# Gate_Driver_H-Bridge.net
KiCad netlist of a schematic drawn in Altium Designer
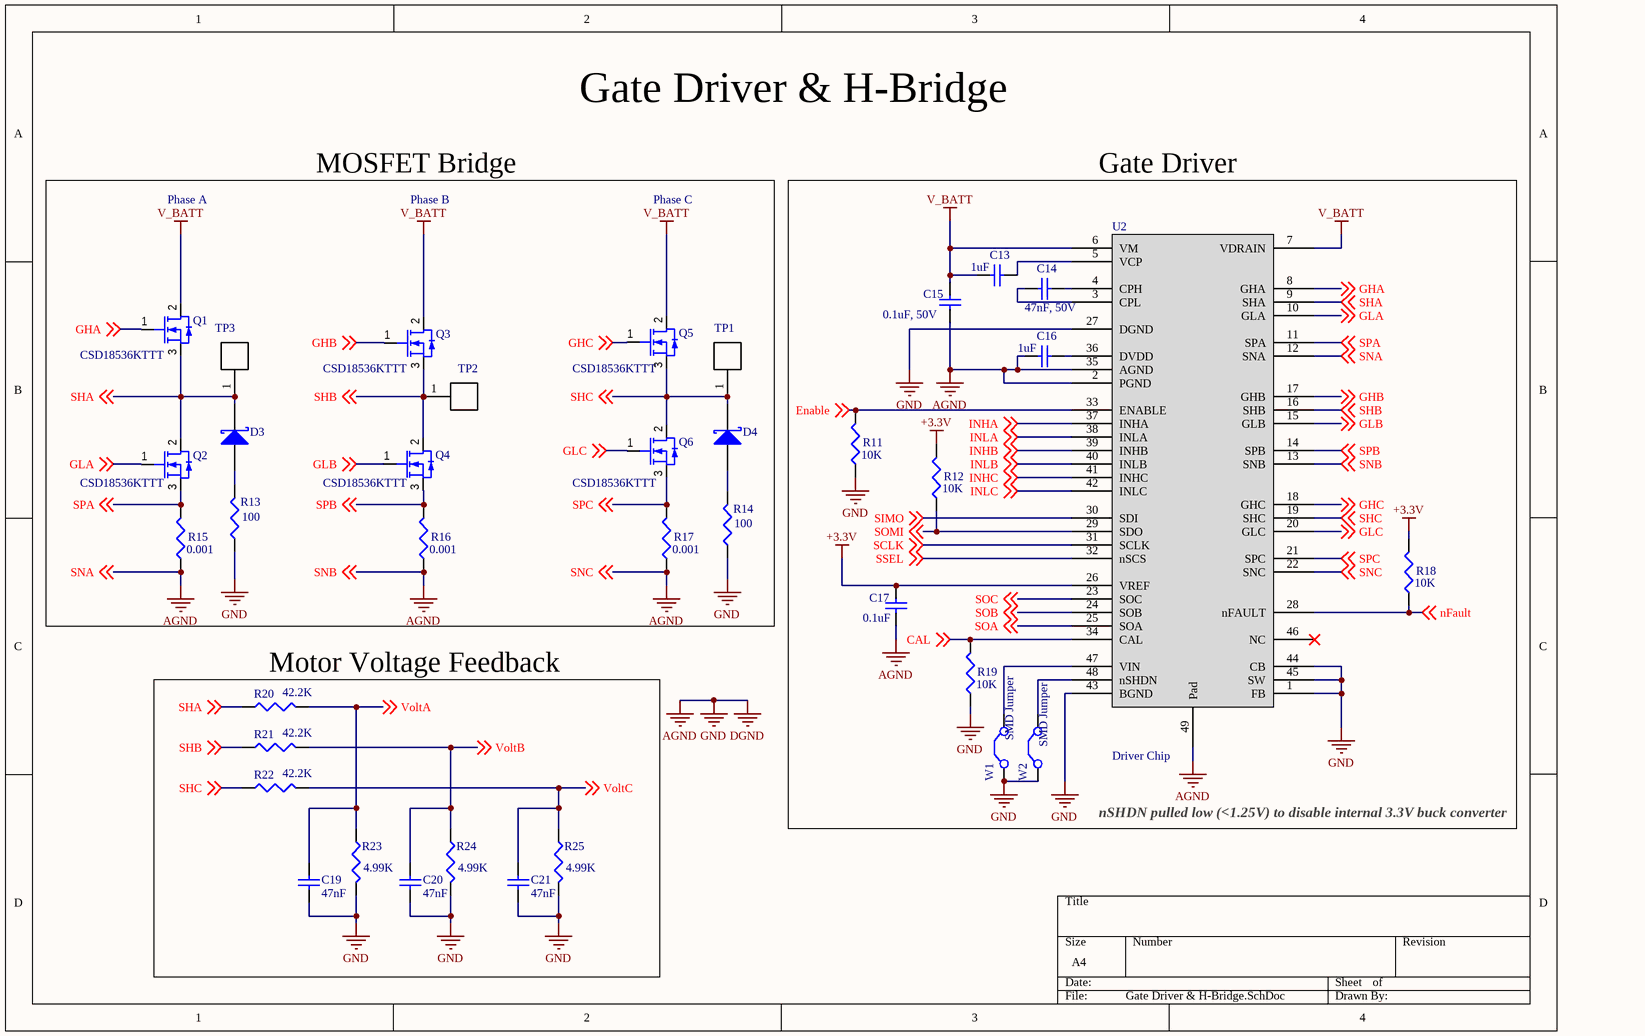
[diagram p0: Gate Driver & H-Bridge.SchDoc]

(export (version "E")
  (design (tool "Eeschema 10.0.6"))
  (components
    (comp (ref "C13")
      (value "1uF")
      (footprint "CAPC2012X06N")
      (description "Capacitor")
      (fields (field (name "Comment") "Cap") (field (name "PUBLISHER") "Altium Limited"))
      (libsource (lib "Miscellaneous Devices") (part "Cap"))
    )
    (comp (ref "C14")
      (value "47nF, 50V")
      (footprint "0603 CAP Medium")
      (description "Capacitor")
      (fields (field (name "Comment") "Cap") (field (name "PUBLISHER") "Altium Limited"))
      (libsource (lib "Miscellaneous Devices") (part "Cap"))
    )
    (comp (ref "C15")
      (value "0.1uF, 50V")
      (footprint "0603 CAP Medium")
      (description "Capacitor")
      (fields (field (name "Comment") "Cap") (field (name "PUBLISHER") "Altium Limited"))
      (libsource (lib "Miscellaneous Devices") (part "Cap"))
    )
    (comp (ref "C16")
      (value "1uF")
      (footprint "CAPC2012X06N")
      (description "Capacitor")
      (fields (field (name "Comment") "Cap") (field (name "PUBLISHER") "Altium Limited"))
      (libsource (lib "Miscellaneous Devices") (part "Cap"))
    )
    (comp (ref "C17")
      (value "0.1uF")
      (footprint "0603 CAP Medium")
      (description "Capacitor")
      (fields (field (name "Comment") "Cap") (field (name "PUBLISHER") "Altium Limited"))
      (libsource (lib "Miscellaneous Devices") (part "Cap"))
    )
    (comp (ref "C19")
      (value "47nF")
      (footprint "0603 CAP Medium")
      (description "Capacitor")
      (fields (field (name "Comment") "Cap") (field (name "PUBLISHER") "Altium Limited"))
      (libsource (lib "Miscellaneous Devices") (part "Cap"))
    )
    (comp (ref "C20")
      (value "47nF")
      (footprint "0603 CAP Medium")
      (description "Capacitor")
      (fields (field (name "Comment") "Cap") (field (name "PUBLISHER") "Altium Limited"))
      (libsource (lib "Miscellaneous Devices") (part "Cap"))
    )
    (comp (ref "C21")
      (value "47nF")
      (footprint "0603 CAP Medium")
      (description "Capacitor")
      (fields (field (name "Comment") "Cap") (field (name "PUBLISHER") "Altium Limited"))
      (libsource (lib "Miscellaneous Devices") (part "Cap"))
    )
    (comp (ref "D3")
      (value "Diode 11DQ03")
      (footprint "Zener")
      (description "Schottky Rectifier")
      (fields (field (name "PUBLISHER") "Altium Limited"))
      (libsource (lib "Miscellaneous Devices") (part "Diode 11DQ03"))
    )
    (comp (ref "D4")
      (value "Diode 11DQ03")
      (footprint "Zener")
      (description "Schottky Rectifier")
      (fields (field (name "PUBLISHER") "Altium Limited"))
      (libsource (lib "Miscellaneous Devices") (part "Diode 11DQ03"))
    )
    (comp (ref "Q1")
      (value "CSD18536KTTT")
      (footprint "DPAK254P1510X470-3M")
      (fields (field (name "MANUFACTURER") "Texas Instruments"))
      (libsource (lib "ECar Reference LIbary") (part "CSD18536KTTT"))
    )
    (comp (ref "Q2")
      (value "CSD18536KTTT")
      (footprint "DPAK254P1510X470-3M")
      (fields (field (name "MANUFACTURER") "Texas Instruments"))
      (libsource (lib "ECar Reference LIbary") (part "CSD18536KTTT"))
    )
    (comp (ref "Q3")
      (value "CSD18536KTTT")
      (footprint "DPAK254P1510X470-3M")
      (fields (field (name "MANUFACTURER") "Texas Instruments"))
      (libsource (lib "ECar Reference LIbary") (part "CSD18536KTTT"))
    )
    (comp (ref "Q4")
      (value "CSD18536KTTT")
      (footprint "DPAK254P1510X470-3M")
      (fields (field (name "MANUFACTURER") "Texas Instruments"))
      (libsource (lib "ECar Reference LIbary") (part "CSD18536KTTT"))
    )
    (comp (ref "Q5")
      (value "CSD18536KTTT")
      (footprint "DPAK254P1510X470-3M")
      (fields (field (name "MANUFACTURER") "Texas Instruments"))
      (libsource (lib "ECar Reference LIbary") (part "CSD18536KTTT"))
    )
    (comp (ref "Q6")
      (value "CSD18536KTTT")
      (footprint "DPAK254P1510X470-3M")
      (fields (field (name "MANUFACTURER") "Texas Instruments"))
      (libsource (lib "ECar Reference LIbary") (part "CSD18536KTTT"))
    )
    (comp (ref "R11")
      (value "10K")
      (footprint "RES 0603 MEDIUM")
      (description "Resistor")
      (fields (field (name "Comment") "Res3") (field (name "PUBLISHER") "Altium Limited"))
      (libsource (lib "Miscellaneous Devices") (part "Res3"))
    )
    (comp (ref "R12")
      (value "10K")
      (footprint "RES 0603 MEDIUM")
      (description "Resistor")
      (fields (field (name "Comment") "Res3") (field (name "PUBLISHER") "Altium Limited"))
      (libsource (lib "Miscellaneous Devices") (part "Res3"))
    )
    (comp (ref "R13")
      (value "100")
      (footprint "RES 0603 MEDIUM")
      (description "Resistor")
      (fields (field (name "Comment") "Res3") (field (name "PUBLISHER") "Altium Limited"))
      (libsource (lib "Miscellaneous Devices") (part "Res3"))
    )
    (comp (ref "R14")
      (value "100")
      (footprint "RES 0603 MEDIUM")
      (description "Resistor")
      (fields (field (name "Comment") "Res3") (field (name "PUBLISHER") "Altium Limited"))
      (libsource (lib "Miscellaneous Devices") (part "Res3"))
    )
    (comp (ref "R15")
      (value "0.001")
      (footprint "RESC8032X08N")
      (description "Resistor")
      (fields (field (name "Comment") "Res3") (field (name "PUBLISHER") "Altium Limited"))
      (libsource (lib "Miscellaneous Devices") (part "Res3"))
    )
    (comp (ref "R16")
      (value "0.001")
      (footprint "RESC8032X08N")
      (description "Resistor")
      (fields (field (name "Comment") "Res3") (field (name "PUBLISHER") "Altium Limited"))
      (libsource (lib "Miscellaneous Devices") (part "Res3"))
    )
    (comp (ref "R17")
      (value "0.001")
      (footprint "RESC8032X08N")
      (description "Resistor")
      (fields (field (name "Comment") "Res3") (field (name "PUBLISHER") "Altium Limited"))
      (libsource (lib "Miscellaneous Devices") (part "Res3"))
    )
    (comp (ref "R18")
      (value "10K")
      (footprint "RES 0603 MEDIUM")
      (description "Resistor")
      (fields (field (name "Comment") "Res3") (field (name "PUBLISHER") "Altium Limited"))
      (libsource (lib "Miscellaneous Devices") (part "Res3"))
    )
    (comp (ref "R19")
      (value "10K")
      (footprint "RES 0603 MEDIUM")
      (description "Resistor")
      (fields (field (name "Comment") "Res3") (field (name "PUBLISHER") "Altium Limited"))
      (libsource (lib "Miscellaneous Devices") (part "Res3"))
    )
    (comp (ref "R20")
      (value "42.2K")
      (footprint "RES 0603 MEDIUM")
      (description "Resistor")
      (fields (field (name "Comment") "Res3") (field (name "PUBLISHER") "Altium Limited"))
      (libsource (lib "Miscellaneous Devices") (part "Res3"))
    )
    (comp (ref "R21")
      (value "42.2K")
      (footprint "RES 0603 MEDIUM")
      (description "Resistor")
      (fields (field (name "Comment") "Res3") (field (name "PUBLISHER") "Altium Limited"))
      (libsource (lib "Miscellaneous Devices") (part "Res3"))
    )
    (comp (ref "R22")
      (value "42.2K")
      (footprint "RES 0603 MEDIUM")
      (description "Resistor")
      (fields (field (name "Comment") "Res3") (field (name "PUBLISHER") "Altium Limited"))
      (libsource (lib "Miscellaneous Devices") (part "Res3"))
    )
    (comp (ref "R23")
      (value "4.99K")
      (footprint "RES 0603 MEDIUM")
      (description "Resistor")
      (fields (field (name "Comment") "Res3") (field (name "PUBLISHER") "Altium Limited"))
      (libsource (lib "Miscellaneous Devices") (part "Res3"))
    )
    (comp (ref "R24")
      (value "4.99K")
      (footprint "RES 0603 MEDIUM")
      (description "Resistor")
      (fields (field (name "Comment") "Res3") (field (name "PUBLISHER") "Altium Limited"))
      (libsource (lib "Miscellaneous Devices") (part "Res3"))
    )
    (comp (ref "R25")
      (value "4.99K")
      (footprint "RES 0603 MEDIUM")
      (description "Resistor")
      (fields (field (name "Comment") "Res3") (field (name "PUBLISHER") "Altium Limited"))
      (libsource (lib "Miscellaneous Devices") (part "Res3"))
    )
    (comp (ref "TP1")
      (value "1625854-3")
      (footprint "TE_RCU-0C")
      (description "0603 PROBE PAD")
      (fields (field (name "MF") "TE Connectivity") (field (name "DIGI-KEY_PART_NUMBER") "A106145CT-ND"))
      (libsource (lib "ECar Reference LIbary") (part "RCU-0C"))
    )
    (comp (ref "TP2")
      (value "1625854-3")
      (footprint "TE_RCU-0C")
      (description "0603 PROBE PAD")
      (fields (field (name "MF") "TE Connectivity") (field (name "DIGI-KEY_PART_NUMBER") "A106145CT-ND"))
      (libsource (lib "ECar Reference LIbary") (part "RCU-0C"))
    )
    (comp (ref "TP3")
      (value "1625854-3")
      (footprint "TE_RCU-0C")
      (description "0603 PROBE PAD")
      (fields (field (name "MF") "TE Connectivity") (field (name "DIGI-KEY_PART_NUMBER") "A106145CT-ND"))
      (libsource (lib "ECar Reference LIbary") (part "RCU-0C"))
    )
    (comp (ref "U2")
      (value "Driver Chip")
      (footprint "QFN50P700X700X100_HS-49N")
      (libsource (lib "MOSFET Board Schematic Library") (part "Driver Chip"))
    )
    (comp (ref "W1")
      (value "SMD Jumper")
      (footprint "SMD Jumper")
      (description "SMD solder jumper")
      (libsource (lib "ECar Reference LIbary") (part "SMD Jumper"))
    )
    (comp (ref "W2")
      (value "SMD Jumper")
      (footprint "SMD Jumper")
      (description "SMD solder jumper")
      (libsource (lib "ECar Reference LIbary") (part "SMD Jumper"))
    )
  )
  (nets
    (net (code "1") (name "+3.3V") (class "Default")
      (node (ref "C17") (pin "2") (pinfunction "2_2") (pintype "passive"))
      (node (ref "R12") (pin "2") (pinfunction "2_2") (pintype "passive"))
      (node (ref "R18") (pin "2") (pinfunction "2_2") (pintype "passive"))
      (node (ref "U2") (pin "26") (pinfunction "VREF_26") (pintype "passive"))
    )
    (net (code "2") (name "AGND") (class "Default")
      (node (ref "C15") (pin "1") (pinfunction "1_1") (pintype "passive"))
      (node (ref "C16") (pin "1") (pinfunction "1_1") (pintype "passive"))
      (node (ref "C17") (pin "1") (pinfunction "1_1") (pintype "passive"))
      (node (ref "C19") (pin "1") (pinfunction "1_1") (pintype "passive"))
      (node (ref "C20") (pin "1") (pinfunction "1_1") (pintype "passive"))
      (node (ref "C21") (pin "1") (pinfunction "1_1") (pintype "passive"))
      (node (ref "R11") (pin "1") (pinfunction "1_1") (pintype "passive"))
      (node (ref "R13") (pin "1") (pinfunction "1_1") (pintype "passive"))
      (node (ref "R14") (pin "1") (pinfunction "1_1") (pintype "passive"))
      (node (ref "R15") (pin "1") (pinfunction "1_1") (pintype "passive"))
      (node (ref "R16") (pin "1") (pinfunction "1_1") (pintype "passive"))
      (node (ref "R17") (pin "1") (pinfunction "1_1") (pintype "passive"))
      (node (ref "R19") (pin "1") (pinfunction "1_1") (pintype "passive"))
      (node (ref "R23") (pin "2") (pinfunction "2_2") (pintype "passive"))
      (node (ref "R24") (pin "2") (pinfunction "2_2") (pintype "passive"))
      (node (ref "R25") (pin "2") (pinfunction "2_2") (pintype "passive"))
      (node (ref "U2") (pin "1") (pinfunction "FB_1") (pintype "passive"))
      (node (ref "U2") (pin "12") (pinfunction "SNA_12") (pintype "passive"))
      (node (ref "U2") (pin "13") (pinfunction "SNB_13") (pintype "passive"))
      (node (ref "U2") (pin "2") (pinfunction "PGND_2") (pintype "passive"))
      (node (ref "U2") (pin "22") (pinfunction "SNC_22") (pintype "passive"))
      (node (ref "U2") (pin "27") (pinfunction "DGND_27") (pintype "passive"))
      (node (ref "U2") (pin "35") (pinfunction "AGND_35") (pintype "passive"))
      (node (ref "U2") (pin "43") (pinfunction "BGND_43") (pintype "passive"))
      (node (ref "U2") (pin "44") (pinfunction "CB_44") (pintype "passive"))
      (node (ref "U2") (pin "45") (pinfunction "SW_45") (pintype "passive"))
      (node (ref "U2") (pin "49") (pinfunction "Pad_49") (pintype "passive"))
      (node (ref "W1") (pin "1") (pinfunction "C1_1") (pintype "passive"))
      (node (ref "W2") (pin "1") (pinfunction "C1_1") (pintype "passive"))
    )
    (net (code "3") (name "CAL") (class "Default")
      (node (ref "R19") (pin "2") (pinfunction "2_2") (pintype "passive"))
      (node (ref "U2") (pin "34") (pinfunction "CAL_34") (pintype "passive"))
    )
    (net (code "4") (name "Enable") (class "Default")
      (node (ref "R11") (pin "2") (pinfunction "2_2") (pintype "passive"))
      (node (ref "U2") (pin "33") (pinfunction "ENABLE_33") (pintype "passive"))
    )
    (net (code "5") (name "GHA") (class "Default")
      (node (ref "Q1") (pin "1") (pinfunction "G_1") (pintype "passive"))
      (node (ref "U2") (pin "8") (pinfunction "GHA_8") (pintype "passive"))
    )
    (net (code "6") (name "GHB") (class "Default")
      (node (ref "Q3") (pin "1") (pinfunction "G_1") (pintype "passive"))
      (node (ref "U2") (pin "17") (pinfunction "GHB_17") (pintype "passive"))
    )
    (net (code "7") (name "GHC") (class "Default")
      (node (ref "Q5") (pin "1") (pinfunction "G_1") (pintype "passive"))
      (node (ref "U2") (pin "18") (pinfunction "GHC_18") (pintype "passive"))
    )
    (net (code "8") (name "GLA") (class "Default")
      (node (ref "Q2") (pin "1") (pinfunction "G_1") (pintype "passive"))
      (node (ref "U2") (pin "10") (pinfunction "GLA_10") (pintype "passive"))
    )
    (net (code "9") (name "GLB") (class "Default")
      (node (ref "Q4") (pin "1") (pinfunction "G_1") (pintype "passive"))
      (node (ref "U2") (pin "15") (pinfunction "GLB_15") (pintype "passive"))
    )
    (net (code "10") (name "GLC") (class "Default")
      (node (ref "Q6") (pin "1") (pinfunction "G_1") (pintype "passive"))
      (node (ref "U2") (pin "20") (pinfunction "GLC_20") (pintype "passive"))
    )
    (net (code "11") (name "INHA") (class "Default")
      (node (ref "U2") (pin "37") (pinfunction "INHA_37") (pintype "passive"))
    )
    (net (code "12") (name "INHB") (class "Default")
      (node (ref "U2") (pin "39") (pinfunction "INHB_39") (pintype "passive"))
    )
    (net (code "13") (name "INHC") (class "Default")
      (node (ref "U2") (pin "41") (pinfunction "INHC_41") (pintype "passive"))
    )
    (net (code "14") (name "INLA") (class "Default")
      (node (ref "U2") (pin "38") (pinfunction "INLA_38") (pintype "passive"))
    )
    (net (code "15") (name "INLB") (class "Default")
      (node (ref "U2") (pin "40") (pinfunction "INLB_40") (pintype "passive"))
    )
    (net (code "16") (name "INLC") (class "Default")
      (node (ref "U2") (pin "42") (pinfunction "INLC_42") (pintype "passive"))
    )
    (net (code "17") (name "Net-(D3-A)") (class "Default")
      (node (ref "D3") (pin "1") (pinfunction "A_1") (pintype "passive"))
      (node (ref "R13") (pin "2") (pinfunction "2_2") (pintype "passive"))
    )
    (net (code "18") (name "Net-(D4-A)") (class "Default")
      (node (ref "D4") (pin "1") (pinfunction "A_1") (pintype "passive"))
      (node (ref "R14") (pin "2") (pinfunction "2_2") (pintype "passive"))
    )
    (net (code "19") (name "Net-(U2-CPH)") (class "Default")
      (node (ref "C14") (pin "2") (pinfunction "2_2") (pintype "passive"))
      (node (ref "U2") (pin "4") (pinfunction "CPH_4") (pintype "passive"))
    )
    (net (code "20") (name "Net-(U2-CPL)") (class "Default")
      (node (ref "C14") (pin "1") (pinfunction "1_1") (pintype "passive"))
      (node (ref "U2") (pin "3") (pinfunction "CPL_3") (pintype "passive"))
    )
    (net (code "21") (name "Net-(U2-DVDD)") (class "Default")
      (node (ref "C16") (pin "2") (pinfunction "2_2") (pintype "passive"))
      (node (ref "U2") (pin "36") (pinfunction "DVDD_36") (pintype "passive"))
    )
    (net (code "22") (name "Net-(U2-VCP)") (class "Default")
      (node (ref "C13") (pin "2") (pinfunction "2_2") (pintype "passive"))
      (node (ref "U2") (pin "5") (pinfunction "VCP_5") (pintype "passive"))
    )
    (net (code "23") (name "Net-(U2-VIN)") (class "Default")
      (node (ref "U2") (pin "47") (pinfunction "VIN_47") (pintype "passive"))
      (node (ref "W1") (pin "2") (pinfunction "C2_2") (pintype "passive"))
    )
    (net (code "24") (name "Net-(U2-nSHDN)") (class "Default")
      (node (ref "U2") (pin "48") (pinfunction "nSHDN_48") (pintype "passive"))
      (node (ref "W2") (pin "2") (pinfunction "C2_2") (pintype "passive"))
    )
    (net (code "25") (name "SCLK") (class "Default")
      (node (ref "U2") (pin "31") (pinfunction "SCLK_31") (pintype "passive"))
    )
    (net (code "26") (name "SHA") (class "Default")
      (node (ref "D3") (pin "2") (pinfunction "K_2") (pintype "passive"))
      (node (ref "Q1") (pin "3") (pinfunction "S_3") (pintype "passive"))
      (node (ref "Q2") (pin "2") (pinfunction "D_2") (pintype "passive"))
      (node (ref "R20") (pin "1") (pinfunction "1_1") (pintype "passive"))
      (node (ref "TP3") (pin "1") (pinfunction "1_1") (pintype "passive"))
      (node (ref "U2") (pin "9") (pinfunction "SHA_9") (pintype "passive"))
    )
    (net (code "27") (name "SHB") (class "Default")
      (node (ref "Q3") (pin "3") (pinfunction "S_3") (pintype "passive"))
      (node (ref "Q4") (pin "2") (pinfunction "D_2") (pintype "passive"))
      (node (ref "R21") (pin "1") (pinfunction "1_1") (pintype "passive"))
      (node (ref "TP2") (pin "1") (pinfunction "1_1") (pintype "passive"))
      (node (ref "U2") (pin "16") (pinfunction "SHB_16") (pintype "passive"))
    )
    (net (code "28") (name "SHC") (class "Default")
      (node (ref "D4") (pin "2") (pinfunction "K_2") (pintype "passive"))
      (node (ref "Q5") (pin "3") (pinfunction "S_3") (pintype "passive"))
      (node (ref "Q6") (pin "2") (pinfunction "D_2") (pintype "passive"))
      (node (ref "R22") (pin "1") (pinfunction "1_1") (pintype "passive"))
      (node (ref "TP1") (pin "1") (pinfunction "1_1") (pintype "passive"))
      (node (ref "U2") (pin "19") (pinfunction "SHC_19") (pintype "passive"))
    )
    (net (code "29") (name "SIMO") (class "Default")
      (node (ref "U2") (pin "30") (pinfunction "SDI_30") (pintype "passive"))
    )
    (net (code "30") (name "SOA") (class "Default")
      (node (ref "U2") (pin "25") (pinfunction "SOA_25") (pintype "passive"))
    )
    (net (code "31") (name "SOB") (class "Default")
      (node (ref "U2") (pin "24") (pinfunction "SOB_24") (pintype "passive"))
    )
    (net (code "32") (name "SOC") (class "Default")
      (node (ref "U2") (pin "23") (pinfunction "SOC_23") (pintype "passive"))
    )
    (net (code "33") (name "SOMI") (class "Default")
      (node (ref "R12") (pin "1") (pinfunction "1_1") (pintype "passive"))
      (node (ref "U2") (pin "29") (pinfunction "SDO_29") (pintype "passive"))
    )
    (net (code "34") (name "SPA") (class "Default")
      (node (ref "Q2") (pin "3") (pinfunction "S_3") (pintype "passive"))
      (node (ref "R15") (pin "2") (pinfunction "2_2") (pintype "passive"))
      (node (ref "U2") (pin "11") (pinfunction "SPA_11") (pintype "passive"))
    )
    (net (code "35") (name "SPB") (class "Default")
      (node (ref "Q4") (pin "3") (pinfunction "S_3") (pintype "passive"))
      (node (ref "R16") (pin "2") (pinfunction "2_2") (pintype "passive"))
      (node (ref "U2") (pin "14") (pinfunction "SPB_14") (pintype "passive"))
    )
    (net (code "36") (name "SPC") (class "Default")
      (node (ref "Q6") (pin "3") (pinfunction "S_3") (pintype "passive"))
      (node (ref "R17") (pin "2") (pinfunction "2_2") (pintype "passive"))
      (node (ref "U2") (pin "21") (pinfunction "SPC_21") (pintype "passive"))
    )
    (net (code "37") (name "SSEL") (class "Default")
      (node (ref "U2") (pin "32") (pinfunction "nSCS_32") (pintype "passive"))
    )
    (net (code "38") (name "V_BATT") (class "Default")
      (node (ref "C13") (pin "1") (pinfunction "1_1") (pintype "passive"))
      (node (ref "C15") (pin "2") (pinfunction "2_2") (pintype "passive"))
      (node (ref "Q1") (pin "2") (pinfunction "D_2") (pintype "passive"))
      (node (ref "Q3") (pin "2") (pinfunction "D_2") (pintype "passive"))
      (node (ref "Q5") (pin "2") (pinfunction "D_2") (pintype "passive"))
      (node (ref "U2") (pin "6") (pinfunction "VM_6") (pintype "passive"))
      (node (ref "U2") (pin "7") (pinfunction "VDRAIN_7") (pintype "passive"))
    )
    (net (code "39") (name "VoltA") (class "Default")
      (node (ref "C19") (pin "2") (pinfunction "2_2") (pintype "passive"))
      (node (ref "R20") (pin "2") (pinfunction "2_2") (pintype "passive"))
      (node (ref "R23") (pin "1") (pinfunction "1_1") (pintype "passive"))
    )
    (net (code "40") (name "VoltB") (class "Default")
      (node (ref "C20") (pin "2") (pinfunction "2_2") (pintype "passive"))
      (node (ref "R21") (pin "2") (pinfunction "2_2") (pintype "passive"))
      (node (ref "R24") (pin "1") (pinfunction "1_1") (pintype "passive"))
    )
    (net (code "41") (name "VoltC") (class "Default")
      (node (ref "C21") (pin "2") (pinfunction "2_2") (pintype "passive"))
      (node (ref "R22") (pin "2") (pinfunction "2_2") (pintype "passive"))
      (node (ref "R25") (pin "1") (pinfunction "1_1") (pintype "passive"))
    )
    (net (code "42") (name "nFault") (class "Default")
      (node (ref "R18") (pin "1") (pinfunction "1_1") (pintype "passive"))
      (node (ref "U2") (pin "28") (pinfunction "nFAULT_28") (pintype "passive"))
    )
    (net (code "43") (name "unconnected-(U2-NC-Pad46)") (class "Default")
      (node (ref "U2") (pin "46") (pinfunction "NC_46") (pintype "passive+no_connect"))
    )
  )
)
